# RTU_LMG_Block_Diagram.net
KiCad netlist of a schematic drawn in Altium Designer
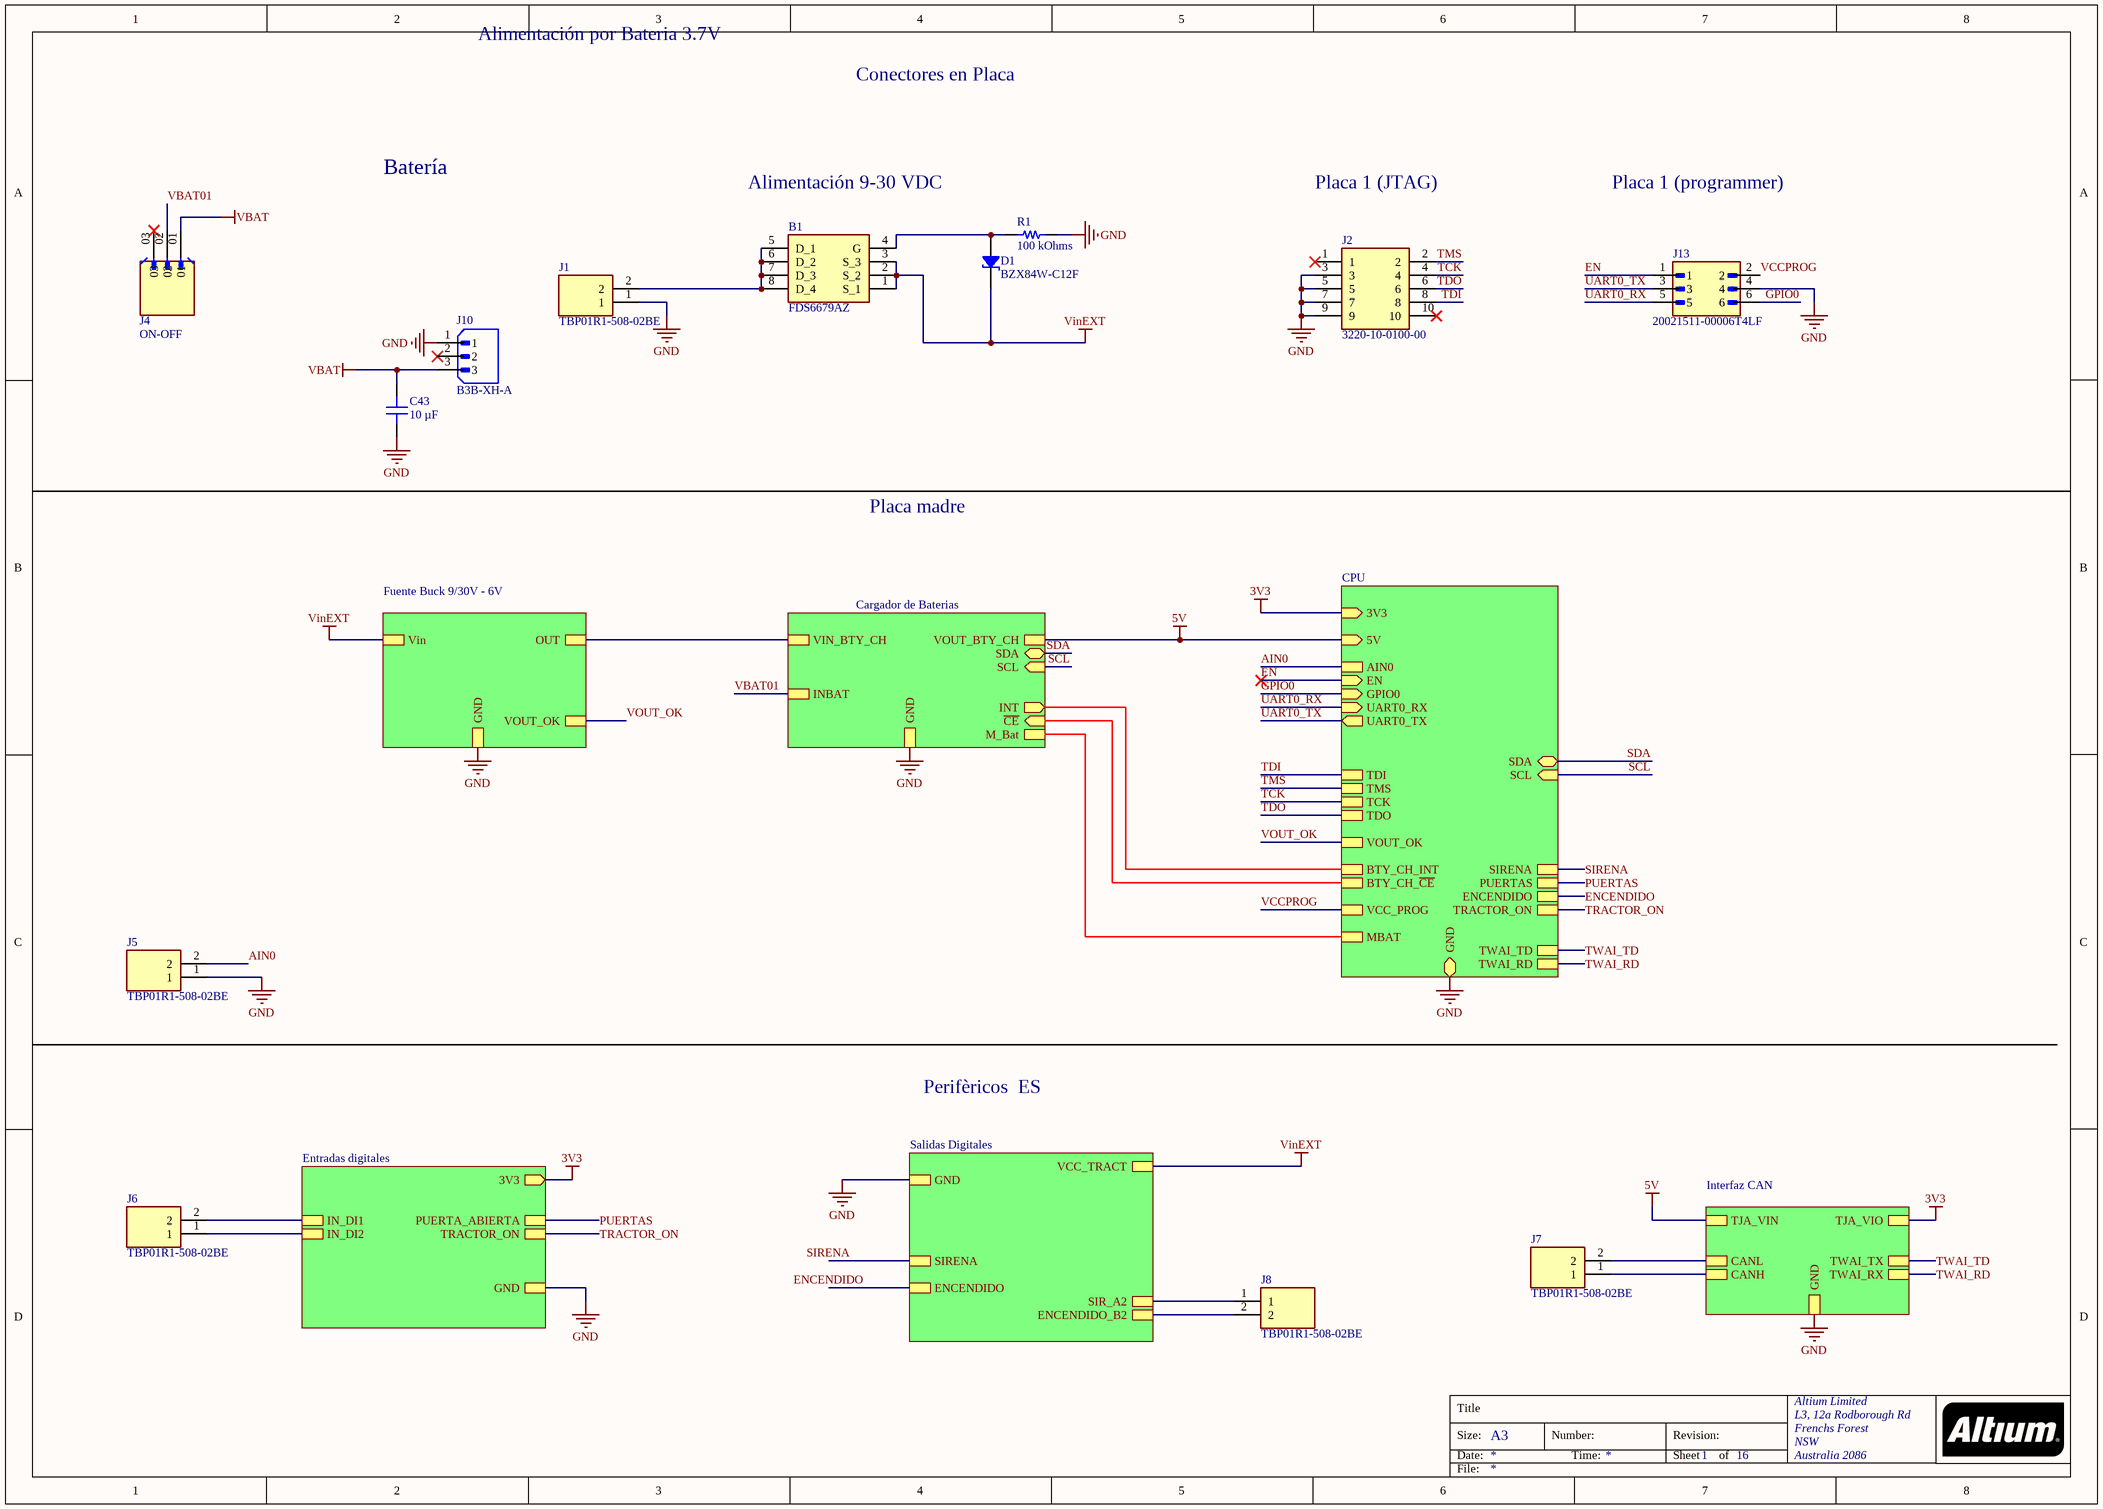
[diagram p0: RTU_LMG_Block_Diagram.SchDoc]

(export (version "E")
  (design (tool "Eeschema 10.0.6"))
  (components
    (comp (ref "B1")
      (value "FDS6679AZ")
      (footprint "SOIC127P600X175-8N:SOIC127P600X175-8N")
      (fields (field (name "MOUSER PART NUMBER") "512-FDS6679AZ"))
      (libsource (lib "FDS6679AZ") (part "FDS6679AZ"))
    )
    (comp (ref "C43")
      (value "10 µF")
      (footprint "PCB - RESISTOR - CHIP - YAGEO RES 0805_2012:YAGEO RES 0805_2012")
      (description "CAP CER 10UF 16V X5R 0805")
      (fields
        (field (name "PART NUMBER") "CL21A106KOQNNNE")
        (field (name "MANUFACTURER") "Samsung Electro-Mechanics")
      )
      (libsource (lib "Celestial Altium Library - altium_library") (part "Capacitor"))
    )
    (comp (ref "D1")
      (value "BZX84W-C12F")
      (footprint "SOT65P210X110-3N")
      (description "DIODE ZENER 12V 275MW SOT323")
      (fields (field (name "MANUFACTURER") "Nexperia USA Inc.") (field (name "TOLERANCE") "±5%"))
      (libsource (lib "Celestial Altium Library - altium_library") (part "Diode Zener"))
    )
    (comp (ref "J1")
      (value "TBP01R1-508-02BE")
      (footprint "CUI_TBP01R1-508-02BE")
      (description "2~24 Poles, Pluggable, Receptacle, Horizontal, 5.08 Pitch, Terminal Block Connector")
      (fields (field (name "MF") "Same Sky"))
      (libsource (lib "TBP01R1-508-02BE") (part "TBP01R1-508-02BE"))
    )
    (comp (ref "J2")
      (value "3220-10-0100-00")
      (footprint "322010010000")
      (description "Connector Header Through Hole 10 position Shrouded 4 wall 0.050\" (1.27mm)")
      (libsource (lib "DIN_DC_Base_Board_components") (part "3220-10-0100-00"))
    )
    (comp (ref "J4")
      (value "ON-OFF")
      (footprint "AMPHENOL_68001-203HLF")
      (fields (field (name "MF") "Amphenol ICC") (field (name "MP") "68001-203HLF"))
      (libsource (lib "68001-203HLF") (part "68001-203HLF"))
    )
    (comp (ref "J5")
      (value "TBP01R1-508-02BE")
      (footprint "CUI_TBP01R1-508-02BE")
      (description "2~24 Poles, Pluggable, Receptacle, Horizontal, 5.08 Pitch, Terminal Block Connector")
      (fields (field (name "MF") "Same Sky"))
      (libsource (lib "TBP01R1-508-02BE") (part "TBP01R1-508-02BE"))
    )
    (comp (ref "J6")
      (value "TBP01R1-508-02BE")
      (footprint "CUI_TBP01R1-508-02BE")
      (description "2~24 Poles, Pluggable, Receptacle, Horizontal, 5.08 Pitch, Terminal Block Connector")
      (fields (field (name "MF") "Same Sky"))
      (libsource (lib "TBP01R1-508-02BE") (part "TBP01R1-508-02BE"))
    )
    (comp (ref "J7")
      (value "TBP01R1-508-02BE")
      (footprint "CUI_TBP01R1-508-02BE")
      (description "2~24 Poles, Pluggable, Receptacle, Horizontal, 5.08 Pitch, Terminal Block Connector")
      (fields (field (name "MF") "Same Sky"))
      (libsource (lib "TBP01R1-508-02BE") (part "TBP01R1-508-02BE"))
    )
    (comp (ref "J8")
      (value "TBP01R1-508-02BE")
      (footprint "CUI_TBP01R1-508-02BE")
      (description "2~24 Poles, Pluggable, Receptacle, Horizontal, 5.08 Pitch, Terminal Block Connector")
      (fields (field (name "MF") "Same Sky"))
      (libsource (lib "") (part "TBP01R1-508-02BE_1"))
    )
    (comp (ref "J10")
      (value "B3B-XH-A")
      (footprint "JST_B3B-XH-A")
      (description "Connector Header Through Hole 3 position 0.098 (2.50mm)")
      (fields (field (name "MF") "JST Sales"))
      (libsource (lib "B3B-XH-A") (part "B3B-XH-A"))
    )
    (comp (ref "J13")
      (value "20021511-00006T4LF")
      (footprint "AMPHENOL_20021511-00006T4LF")
      (description "1.27mm (0.05in.) pitch, Shrouded header, 6 contacts")
      (fields (field (name "MF") "Amphenol ICC (FCI)"))
      (libsource (lib "DIN_DC_Base_Board_components") (part "20021511-00006T4LF"))
    )
    (comp (ref "R1")
      (value "100 kOhms")
      (footprint "RES 0603_1608")
      (description "RES 100K OHM 0.1% 1/16W 0603")
      (fields
        (field (name "PART NUMBER") "RNCS0603BKE100K")
        (field (name "MANUFACTURER") "Stackpole Electronics Inc")
      )
      (libsource (lib "Celestial Altium Library - altium_library") (part "Resistor"))
    )
  )
  (nets
    (net (code "1") (name "/AIN0") (class "Default")
      (node (ref "J5") (pin "2") (pinfunction "2_2") (pintype "passive"))
    )
    (net (code "3") (name "/CANH") (class "Default")
      (node (ref "J7") (pin "1") (pinfunction "1_1") (pintype "passive"))
    )
    (net (code "4") (name "/CANL") (class "Default")
      (node (ref "J7") (pin "2") (pinfunction "2_2") (pintype "passive"))
    )
    (net (code "5") (name "/EN") (class "Default")
      (node (ref "J13") (pin "1") (pinfunction "1_1") (pintype "passive+no_connect"))
    )
    (net (code "7") (name "/ENCENDIDO_B2") (class "Default")
      (node (ref "J8") (pin "2") (pinfunction "2_2") (pintype "passive"))
    )
    (net (code "8") (name "/GPIO0") (class "Default")
      (node (ref "J13") (pin "6") (pinfunction "6_6") (pintype "passive"))
    )
    (net (code "10") (name "/IN_DI1") (class "Default")
      (node (ref "J6") (pin "2") (pinfunction "2_2") (pintype "passive"))
    )
    (net (code "11") (name "/IN_DI2") (class "Default")
      (node (ref "J6") (pin "1") (pinfunction "1_1") (pintype "passive"))
    )
    (net (code "18") (name "/SIR_A2") (class "Default")
      (node (ref "J8") (pin "1") (pinfunction "1_1") (pintype "passive"))
    )
    (net (code "19") (name "/TCK") (class "Default")
      (node (ref "J2") (pin "4") (pinfunction "4_4") (pintype "passive"))
    )
    (net (code "20") (name "/TDI") (class "Default")
      (node (ref "J2") (pin "8") (pinfunction "8_8") (pintype "passive"))
    )
    (net (code "21") (name "/TDO") (class "Default")
      (node (ref "J2") (pin "6") (pinfunction "6_6") (pintype "passive"))
    )
    (net (code "22") (name "/TMS") (class "Default")
      (node (ref "J2") (pin "2") (pinfunction "2_2") (pintype "passive"))
    )
    (net (code "26") (name "/UART0_RX") (class "Default")
      (node (ref "J13") (pin "5") (pinfunction "5_5") (pintype "passive"))
    )
    (net (code "27") (name "/UART0_TX") (class "Default")
      (node (ref "J13") (pin "3") (pinfunction "3_3") (pintype "passive"))
    )
    (net (code "28") (name "/VBAT01") (class "Default")
      (node (ref "J4") (pin "02") (pinfunction "02_02") (pintype "passive"))
    )
    (net (code "29") (name "/VCCPROG") (class "Default")
      (node (ref "J13") (pin "2") (pinfunction "2_2") (pintype "passive"))
    )
    (net (code "33") (name "GND") (class "Default")
      (node (ref "C43") (pin "1") (pinfunction "1_1") (pintype "passive"))
      (node (ref "J1") (pin "1") (pinfunction "1_1") (pintype "passive"))
      (node (ref "J10") (pin "1") (pinfunction "1_1") (pintype "passive"))
      (node (ref "J13") (pin "4") (pinfunction "4_4") (pintype "passive"))
      (node (ref "J2") (pin "3") (pinfunction "3_3") (pintype "passive"))
      (node (ref "J2") (pin "5") (pinfunction "5_5") (pintype "passive"))
      (node (ref "J2") (pin "7") (pinfunction "7_7") (pintype "passive"))
      (node (ref "J2") (pin "9") (pinfunction "9_9") (pintype "passive"))
      (node (ref "J5") (pin "1") (pinfunction "1_1") (pintype "passive"))
      (node (ref "R1") (pin "1") (pinfunction "1_1") (pintype "passive"))
    )
    (net (code "34") (name "Net-(B1-D_1)") (class "Default")
      (node (ref "B1") (pin "5") (pinfunction "D_1_5") (pintype "passive"))
      (node (ref "B1") (pin "6") (pinfunction "D_2_6") (pintype "passive"))
      (node (ref "B1") (pin "7") (pinfunction "D_3_7") (pintype "passive"))
      (node (ref "B1") (pin "8") (pinfunction "D_4_8") (pintype "passive"))
      (node (ref "J1") (pin "2") (pinfunction "2_2") (pintype "passive"))
    )
    (net (code "35") (name "Net-(B1-G)") (class "Default")
      (node (ref "B1") (pin "4") (pinfunction "G_4") (pintype "passive"))
      (node (ref "D1") (pin "1") (pinfunction "1_1") (pintype "passive"))
      (node (ref "R1") (pin "2") (pinfunction "2_2") (pintype "passive"))
    )
    (net (code "36") (name "VBAT") (class "Default")
      (node (ref "C43") (pin "2") (pinfunction "2_2") (pintype "passive"))
      (node (ref "J10") (pin "3") (pinfunction "3_3") (pintype "passive"))
      (node (ref "J4") (pin "01") (pinfunction "01_01") (pintype "passive"))
    )
    (net (code "37") (name "VinEXT") (class "Default")
      (node (ref "B1") (pin "1") (pinfunction "S_1_1") (pintype "passive"))
      (node (ref "B1") (pin "2") (pinfunction "S_2_2") (pintype "passive"))
      (node (ref "B1") (pin "3") (pinfunction "S_3_3") (pintype "passive"))
      (node (ref "D1") (pin "2") (pinfunction "2_2") (pintype "passive"))
    )
    (net (code "38") (name "unconnected-(J2-Pad1)") (class "Default")
      (node (ref "J2") (pin "1") (pinfunction "1_1") (pintype "passive+no_connect"))
    )
    (net (code "39") (name "unconnected-(J2-Pad10)") (class "Default")
      (node (ref "J2") (pin "10") (pinfunction "10_10") (pintype "passive+no_connect"))
    )
    (net (code "40") (name "unconnected-(J4-Pad03)") (class "Default")
      (node (ref "J4") (pin "03") (pinfunction "03_03") (pintype "passive+no_connect"))
    )
    (net (code "41") (name "unconnected-(J10-Pad2)") (class "Default")
      (node (ref "J10") (pin "2") (pinfunction "2_2") (pintype "passive+no_connect"))
    )
  )
)
